# ADC088S022.net
KiCad netlist of a schematic drawn in Altium Designer
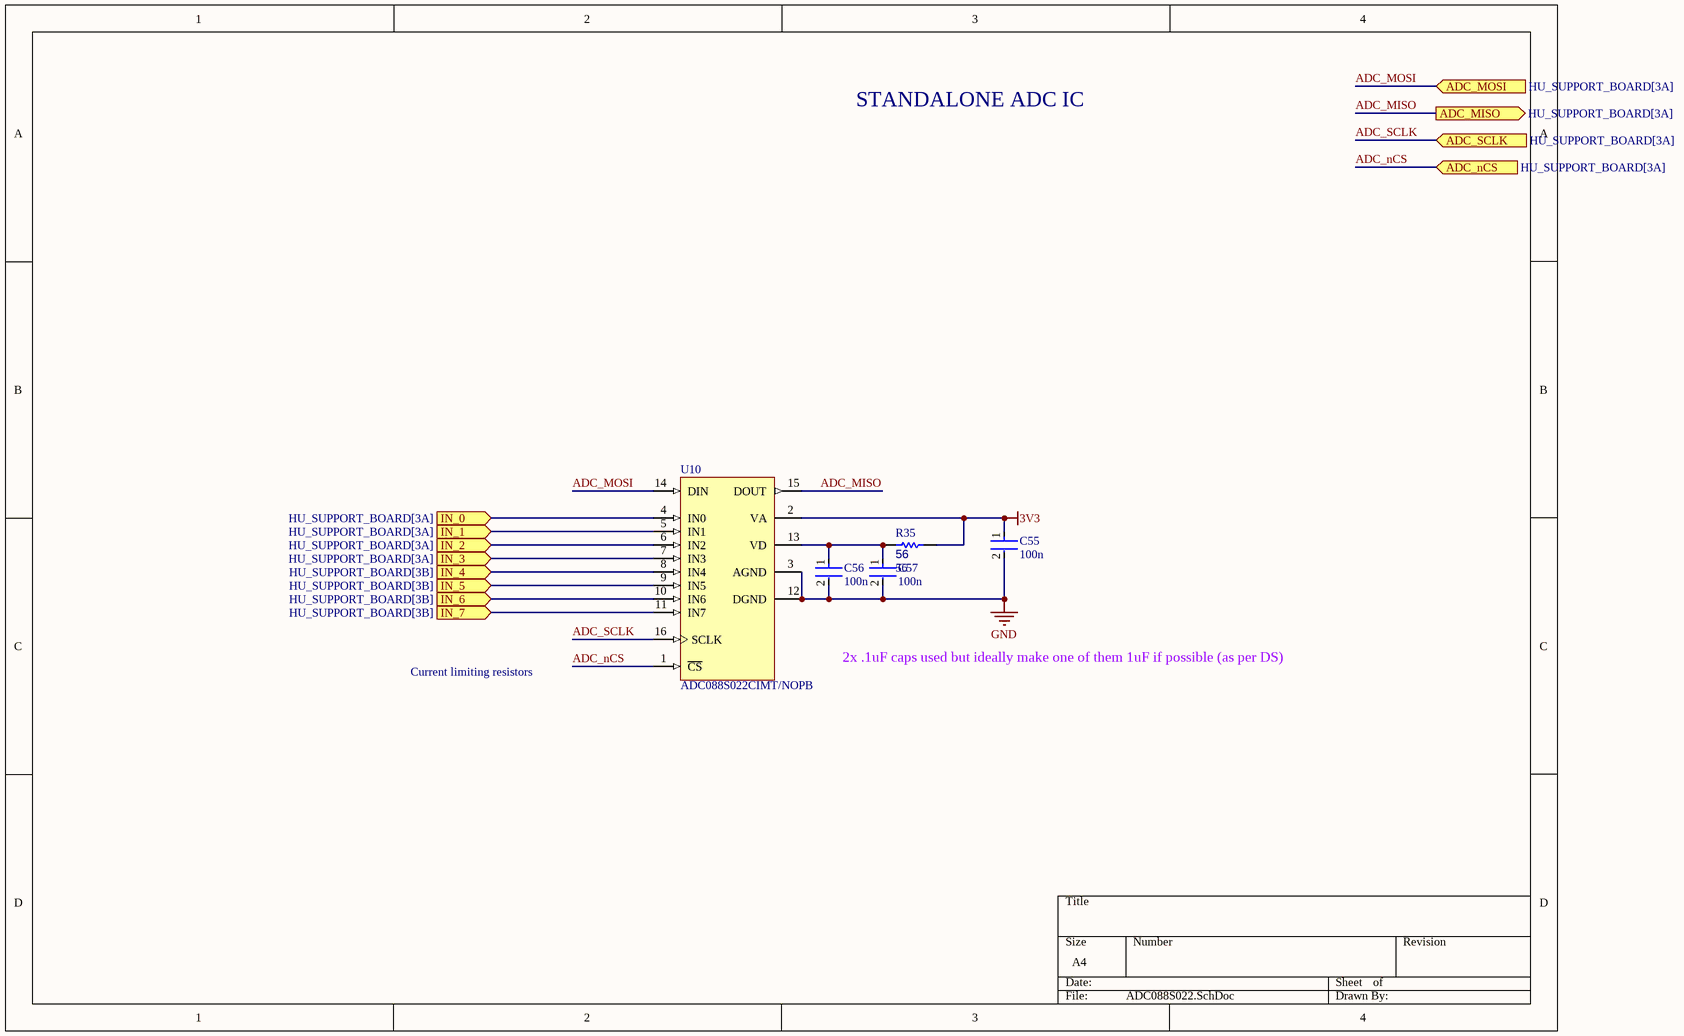
[diagram p0: ADC088S022.SchDoc]

(export (version "E")
  (design (tool "Eeschema 10.0.6"))
  (components
    (comp (ref "C55")
      (value "100n")
      (footprint "FP-0402-L_1_0_0_05-W_0_5-IPC_A")
      (description "LARGE PADS, 0402 CAP, CHANGE COMMENT TO MATCH REAL P/N")
      (libsource (lib "Space Concordia") (part "b4654b650e69147ec39a6b967a45e02"))
    )
    (comp (ref "C56")
      (value "100n")
      (footprint "FP-0402-L_1_0_0_05-W_0_5-IPC_A")
      (description "LARGE PADS, 0402 CAP, CHANGE COMMENT TO MATCH REAL P/N")
      (libsource (lib "Space Concordia") (part "b4654b650e69147ec39a6b967a45e02"))
    )
    (comp (ref "C57")
      (value "100n")
      (footprint "FP-0402-L_1_0_0_05-W_0_5-IPC_A")
      (description "LARGE PADS, 0402 CAP, CHANGE COMMENT TO MATCH REAL P/N")
      (libsource (lib "Space Concordia") (part "b4654b650e69147ec39a6b967a45e02"))
    )
    (comp (ref "R35")
      (value "56")
      (footprint "R0603B")
      (description "Resistor")
      (fields (field (name "ALTIUM_VALUE") "56"))
      (libsource (lib "Space Concordia") (part "Resistor"))
    )
    (comp (ref "U10")
      (value "ADC088S022CIMT/NOPB")
      (footprint "MTC16_L")
      (description "8-Channel, 50 kSPS to 200 kSPS, 8-Bit A/D Converter, 16-pin TSSOP, Pb-Free")
      (fields (field (name "MANUFACTURER") "National Semiconductor"))
      (libsource (lib "Altium Content Vault") (part "CON-ADC-ADC108S052CIMT"))
    )
  )
  (nets
    (net (code "1") (name "/ADC_MISO") (class "Default")
      (node (ref "U10") (pin "15") (pinfunction "DOUT_15") (pintype "output"))
    )
    (net (code "2") (name "/ADC_MOSI") (class "Default")
      (node (ref "U10") (pin "14") (pinfunction "DIN_14") (pintype "input"))
    )
    (net (code "3") (name "/ADC_SCLK") (class "Default")
      (node (ref "U10") (pin "16") (pinfunction "SCLK_16") (pintype "input"))
    )
    (net (code "4") (name "/ADC_nCS") (class "Default")
      (node (ref "U10") (pin "1") (pinfunction "~{CS}_1") (pintype "input"))
    )
    (net (code "5") (name "/IN_0") (class "Default")
      (node (ref "U10") (pin "4") (pinfunction "IN0_4") (pintype "input"))
    )
    (net (code "6") (name "/IN_1") (class "Default")
      (node (ref "U10") (pin "5") (pinfunction "IN1_5") (pintype "input"))
    )
    (net (code "7") (name "/IN_2") (class "Default")
      (node (ref "U10") (pin "6") (pinfunction "IN2_6") (pintype "input"))
    )
    (net (code "8") (name "/IN_3") (class "Default")
      (node (ref "U10") (pin "7") (pinfunction "IN3_7") (pintype "input"))
    )
    (net (code "9") (name "/IN_4") (class "Default")
      (node (ref "U10") (pin "8") (pinfunction "IN4_8") (pintype "input"))
    )
    (net (code "10") (name "/IN_5") (class "Default")
      (node (ref "U10") (pin "9") (pinfunction "IN5_9") (pintype "input"))
    )
    (net (code "11") (name "/IN_6") (class "Default")
      (node (ref "U10") (pin "10") (pinfunction "IN6_10") (pintype "input"))
    )
    (net (code "12") (name "/IN_7") (class "Default")
      (node (ref "U10") (pin "11") (pinfunction "IN7_11") (pintype "input"))
    )
    (net (code "13") (name "3V3") (class "Default")
      (node (ref "C55") (pin "1") (pinfunction "1_1") (pintype "passive"))
      (node (ref "R35") (pin "1") (pinfunction "1_1") (pintype "passive"))
      (node (ref "U10") (pin "2") (pinfunction "VA_2") (pintype "power_in"))
    )
    (net (code "14") (name "GND") (class "Default")
      (node (ref "C55") (pin "2") (pinfunction "2_2") (pintype "passive"))
      (node (ref "C56") (pin "2") (pinfunction "2_2") (pintype "passive"))
      (node (ref "C57") (pin "2") (pinfunction "2_2") (pintype "passive"))
      (node (ref "U10") (pin "12") (pinfunction "DGND_12") (pintype "power_in"))
      (node (ref "U10") (pin "3") (pinfunction "AGND_3") (pintype "power_in"))
    )
    (net (code "15") (name "Net-(U10-VD)") (class "Default")
      (node (ref "C56") (pin "1") (pinfunction "1_1") (pintype "passive"))
      (node (ref "C57") (pin "1") (pinfunction "1_1") (pintype "passive"))
      (node (ref "R35") (pin "2") (pinfunction "2_2") (pintype "passive"))
      (node (ref "U10") (pin "13") (pinfunction "VD_13") (pintype "power_in"))
    )
  )
)
